# PWR.net
KiCad netlist of a schematic drawn in Altium Designer
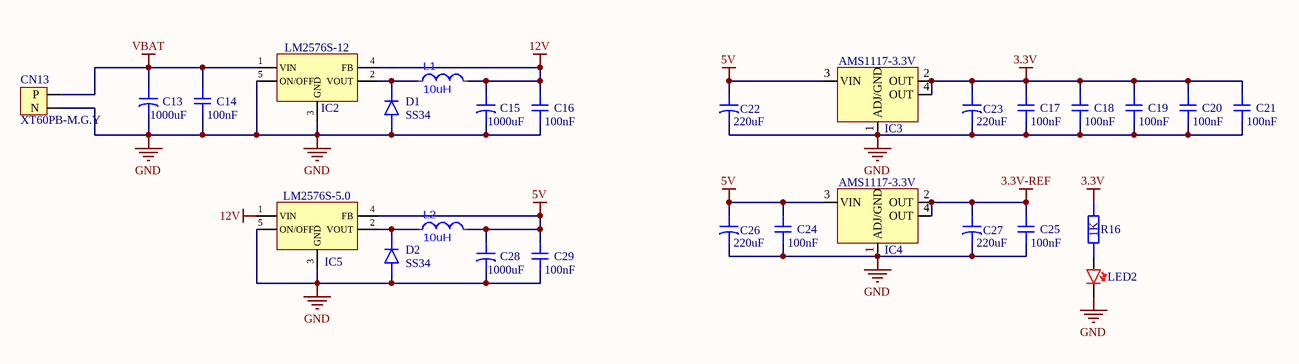
[diagram p0: PWR.SchDoc]

(export (version "E")
  (design (tool "Eeschema 10.0.6"))
  (components
    (comp (ref "C13")
      (value "1000uF")
      (footprint "Plugin,D10xL20mm")
      (description "1000uF 35V Aluminum Electrolytic Capacitors Through Hole,D10xL20mm 2000hrs@105℃")
      (fields (field (name "MANUFACTURER") "Rubycon") (field (name "MFR.PART #") "35PX1000MEFC10X20"))
      (libsource (lib "CbyP") (part "35PX1000MEFC10X20"))
    )
    (comp (ref "C14")
      (value "100nF")
      (footprint "CAP-0603-2")
      (description "100nF ±10% 50V Ceramic Capacitor X7R 0603")
      (fields (field (name "MANUFACTURER") "Samsung Electro-Mechanics") (field (name "LCSC PART #") "C1591"))
      (libsource (lib "CbyP") (part "CL10B104KB8NNNC"))
    )
    (comp (ref "C15")
      (value "1000uF")
      (footprint "Plugin,D10xL20mm")
      (description "1000uF 35V Aluminum Electrolytic Capacitors Through Hole,D10xL20mm 2000hrs@105℃")
      (fields (field (name "MANUFACTURER") "Rubycon") (field (name "MFR.PART #") "35PX1000MEFC10X20"))
      (libsource (lib "CbyP") (part "35PX1000MEFC10X20"))
    )
    (comp (ref "C16")
      (value "100nF")
      (footprint "CAP-0603-2")
      (description "100nF ±10% 50V Ceramic Capacitor X7R 0603")
      (fields (field (name "MANUFACTURER") "Samsung Electro-Mechanics") (field (name "LCSC PART #") "C1591"))
      (libsource (lib "CbyP") (part "CL10B104KB8NNNC"))
    )
    (comp (ref "C17")
      (value "100nF")
      (footprint "CAP-0603-2")
      (description "100nF ±10% 50V Ceramic Capacitor X7R 0603")
      (fields (field (name "MANUFACTURER") "Samsung Electro-Mechanics") (field (name "LCSC PART #") "C1591"))
      (libsource (lib "CbyP") (part "CL10B104KB8NNNC"))
    )
    (comp (ref "C18")
      (value "100nF")
      (footprint "CAP-0603-2")
      (description "100nF ±10% 50V Ceramic Capacitor X7R 0603")
      (fields (field (name "MANUFACTURER") "Samsung Electro-Mechanics") (field (name "LCSC PART #") "C1591"))
      (libsource (lib "CbyP") (part "CL10B104KB8NNNC"))
    )
    (comp (ref "C19")
      (value "100nF")
      (footprint "CAP-0603-2")
      (description "100nF ±10% 50V Ceramic Capacitor X7R 0603")
      (fields (field (name "MANUFACTURER") "Samsung Electro-Mechanics") (field (name "LCSC PART #") "C1591"))
      (libsource (lib "CbyP") (part "CL10B104KB8NNNC"))
    )
    (comp (ref "C20")
      (value "100nF")
      (footprint "CAP-0603-2")
      (description "100nF ±10% 50V Ceramic Capacitor X7R 0603")
      (fields (field (name "MANUFACTURER") "Samsung Electro-Mechanics") (field (name "LCSC PART #") "C1591"))
      (libsource (lib "CbyP") (part "CL10B104KB8NNNC"))
    )
    (comp (ref "C21")
      (value "100nF")
      (footprint "CAP-0603-2")
      (description "100nF ±10% 50V Ceramic Capacitor X7R 0603")
      (fields (field (name "MANUFACTURER") "Samsung Electro-Mechanics") (field (name "LCSC PART #") "C1591"))
      (libsource (lib "CbyP") (part "CL10B104KB8NNNC"))
    )
    (comp (ref "C22")
      (value "220uF")
      (footprint "PLUGIN,D6.3xL12mm")
      (description "220uF 25V Aluminum Electrolytic Capacitors Through Hole,D6.3xL11mm 7000hrs@105℃")
      (fields (field (name "MANUFACTURER") "Rubycon") (field (name "MFR.PART #") "25YXJ220M6.3X11"))
      (libsource (lib "CbyP") (part "25YXJ220M6.3X11"))
    )
    (comp (ref "C23")
      (value "220uF")
      (footprint "PLUGIN,D6.3xL12mm")
      (description "220uF 25V Aluminum Electrolytic Capacitors Through Hole,D6.3xL11mm 7000hrs@105℃")
      (fields (field (name "MANUFACTURER") "Rubycon") (field (name "MFR.PART #") "25YXJ220M6.3X11"))
      (libsource (lib "CbyP") (part "25YXJ220M6.3X11"))
    )
    (comp (ref "C24")
      (value "100nF")
      (footprint "CAP-0603-2")
      (description "100nF ±10% 50V Ceramic Capacitor X7R 0603")
      (fields (field (name "MANUFACTURER") "Samsung Electro-Mechanics") (field (name "LCSC PART #") "C1591"))
      (libsource (lib "CbyP") (part "CL10B104KB8NNNC"))
    )
    (comp (ref "C25")
      (value "100nF")
      (footprint "CAP-0603-2")
      (description "100nF ±10% 50V Ceramic Capacitor X7R 0603")
      (fields (field (name "MANUFACTURER") "Samsung Electro-Mechanics") (field (name "LCSC PART #") "C1591"))
      (libsource (lib "CbyP") (part "CL10B104KB8NNNC"))
    )
    (comp (ref "C26")
      (value "220uF")
      (footprint "PLUGIN,D6.3xL12mm")
      (description "220uF 25V Aluminum Electrolytic Capacitors Through Hole,D6.3xL11mm 7000hrs@105℃")
      (fields (field (name "MANUFACTURER") "Rubycon") (field (name "MFR.PART #") "25YXJ220M6.3X11"))
      (libsource (lib "CbyP") (part "25YXJ220M6.3X11"))
    )
    (comp (ref "C27")
      (value "220uF")
      (footprint "PLUGIN,D6.3xL12mm")
      (description "220uF 25V Aluminum Electrolytic Capacitors Through Hole,D6.3xL11mm 7000hrs@105℃")
      (fields (field (name "MANUFACTURER") "Rubycon") (field (name "MFR.PART #") "25YXJ220M6.3X11"))
      (libsource (lib "CbyP") (part "25YXJ220M6.3X11"))
    )
    (comp (ref "C28")
      (value "1000uF")
      (footprint "Plugin,D10xL20mm")
      (description "1000uF 35V Aluminum Electrolytic Capacitors Through Hole,D10xL20mm 2000hrs@105℃")
      (fields (field (name "MANUFACTURER") "Rubycon") (field (name "MFR.PART #") "35PX1000MEFC10X20"))
      (libsource (lib "CbyP") (part "35PX1000MEFC10X20"))
    )
    (comp (ref "C29")
      (value "100nF")
      (footprint "CAP-0603-2")
      (description "100nF ±10% 50V Ceramic Capacitor X7R 0603")
      (fields (field (name "MANUFACTURER") "Samsung Electro-Mechanics") (field (name "LCSC PART #") "C1591"))
      (libsource (lib "CbyP") (part "CL10B104KB8NNNC"))
    )
    (comp (ref "CN13")
      (value "XT60PB-M.G.Y")
      (footprint "XT60PB-M.G.Y")
      (description "Power Connectors RoHS")
      (fields (field (name "MANUFACTURER") "Changzhou Amass Elec") (field (name "LCSC PART #") "C19268037"))
      (libsource (lib "CbyP") (part "XT60PB-M.G.Y"))
    )
    (comp (ref "D1")
      (value "SS34")
      (footprint "SMA(DO-214AC)")
      (description "Diode Independent 40V 3A Surface Mount SMA(DO-214AC)")
      (fields (field (name "MANUFACTURER") "GOODWORK") (field (name "LCSC PART #") "C908680"))
      (libsource (lib "CbyP") (part "SS34"))
    )
    (comp (ref "D2")
      (value "SS34")
      (footprint "SMA(DO-214AC)")
      (description "Diode Independent 40V 3A Surface Mount SMA(DO-214AC)")
      (fields (field (name "MANUFACTURER") "GOODWORK") (field (name "LCSC PART #") "C908680"))
      (libsource (lib "CbyP") (part "SS34"))
    )
    (comp (ref "IC2")
      (value "LM2576S-12")
      (footprint "TO-263-5L")
      (description "Buck Switching Regulator IC Fixed 12V 1 Output 3A TO-263-5L")
      (fields (field (name "MANUFACTURER") "HXY MOSFET") (field (name "LCSC PART #") "C22386541"))
      (libsource (lib "CbyP") (part "LM2576S-12"))
    )
    (comp (ref "IC3")
      (value "AMS1117-3.3V")
      (footprint "SOT-223")
      (description "Linear Voltage Regulator IC Positive Fixed 1 Output 1A SOT-223")
      (fields (field (name "MANUFACTURER") "MSKSEMI") (field (name "LCSC PART #") "C5120765"))
      (libsource (lib "CbyP") (part "AMS1117-3.3V"))
    )
    (comp (ref "IC4")
      (value "AMS1117-3.3V")
      (footprint "SOT-223")
      (description "Linear Voltage Regulator IC Positive Fixed 1 Output 1A SOT-223")
      (fields (field (name "MANUFACTURER") "MSKSEMI") (field (name "LCSC PART #") "C5120765"))
      (libsource (lib "CbyP") (part "AMS1117-3.3V"))
    )
    (comp (ref "IC5")
      (value "LM2576S-5.0")
      (footprint "TO-263-5L")
      (description "47kHz~58kHz Buck Adjustable 3.5A 5V TO-263-5L Voltage Regulators - DC DC Switching Regulators RoHS")
      (fields (field (name "MANUFACTURER") "HXY MOSFET") (field (name "LCSC PART #") "C5349983"))
      (libsource (lib "CbyP") (part "LM2576S-5.0"))
    )
    (comp (ref "L1")
      (value "10uH")
      (footprint "Inductor 4.5A 10uH 0630")
      (description "4.5A 10uH ±20% 5.5A 68mΩ Molded Inductor SMD,7.3x6.6mm Fixed Inductors RoHS")
      (fields (field (name "MANUFACTURER") "Shun Xiang Nuo") (field (name "MPN") "SMMS0630-100M"))
      (libsource (lib "XE_BIA") (part "Inductor 4.5A 10uH 0630"))
    )
    (comp (ref "L2")
      (value "10uH")
      (footprint "Inductor 4.5A 10uH 0630")
      (description "4.5A 10uH ±20% 5.5A 68mΩ Molded Inductor SMD,7.3x6.6mm Fixed Inductors RoHS")
      (fields (field (name "MANUFACTURER") "Shun Xiang Nuo") (field (name "MPN") "SMMS0630-100M"))
      (libsource (lib "XE_BIA") (part "Inductor 4.5A 10uH 0630"))
    )
    (comp (ref "LED2")
      (value "RED")
      (footprint "LED-0603")
      (description "25mA 1.8V~2.4V Red 0603 LED Indication - Discrete ROHS")
      (fields (field (name "MANUFACTURER") "YONGYUTAI") (field (name "MFR.PART #") "YLED0603R"))
      (libsource (lib "CbyP") (part "YLED0603R"))
    )
    (comp (ref "R16")
      (value "1K")
      (footprint "RES-0603-1")
      (description "100mW 1kΩ 75V Thick Film Resistor ±100ppm/℃ ±1% 0603 Chip Resistor - Surface Mount RoHS")
      (fields (field (name "MANUFACTURER") "YAGEO") (field (name "MFR.PART #") "RC0603FR-071KL"))
      (libsource (lib "CbyP") (part "RC0603FR-071KL"))
    )
  )
  (nets
    (net (code "1") (name "3.3V") (class "Default")
      (node (ref "C17") (pin "1") (pinfunction "1_1") (pintype "passive"))
      (node (ref "C18") (pin "1") (pinfunction "1_1") (pintype "passive"))
      (node (ref "C19") (pin "1") (pinfunction "1_1") (pintype "passive"))
      (node (ref "C20") (pin "1") (pinfunction "1_1") (pintype "passive"))
      (node (ref "C21") (pin "1") (pinfunction "1_1") (pintype "passive"))
      (node (ref "C23") (pin "1") (pinfunction "1_1") (pintype "passive"))
      (node (ref "IC3") (pin "2") (pinfunction "OUT_2") (pintype "passive"))
      (node (ref "IC3") (pin "4") (pinfunction "OUT_4") (pintype "passive"))
      (node (ref "R16") (pin "2") (pinfunction "2_2") (pintype "passive"))
    )
    (net (code "2") (name "3.3V-REF") (class "Default")
      (node (ref "C25") (pin "1") (pinfunction "1_1") (pintype "passive"))
      (node (ref "C27") (pin "1") (pinfunction "1_1") (pintype "passive"))
      (node (ref "IC4") (pin "2") (pinfunction "OUT_2") (pintype "passive"))
      (node (ref "IC4") (pin "4") (pinfunction "OUT_4") (pintype "passive"))
    )
    (net (code "3") (name "5V") (class "Default")
      (node (ref "C22") (pin "1") (pinfunction "1_1") (pintype "passive"))
      (node (ref "C24") (pin "1") (pinfunction "1_1") (pintype "passive"))
      (node (ref "C26") (pin "1") (pinfunction "1_1") (pintype "passive"))
      (node (ref "C28") (pin "1") (pinfunction "1_1") (pintype "passive"))
      (node (ref "C29") (pin "1") (pinfunction "1_1") (pintype "passive"))
      (node (ref "IC3") (pin "3") (pinfunction "VIN_3") (pintype "passive"))
      (node (ref "IC4") (pin "3") (pinfunction "VIN_3") (pintype "passive"))
      (node (ref "IC5") (pin "4") (pinfunction "FB_4") (pintype "passive"))
      (node (ref "L2") (pin "2") (pinfunction "2_2") (pintype "passive"))
    )
    (net (code "4") (name "12V") (class "Default")
      (node (ref "C15") (pin "1") (pinfunction "1_1") (pintype "passive"))
      (node (ref "C16") (pin "1") (pinfunction "1_1") (pintype "passive"))
      (node (ref "IC2") (pin "4") (pinfunction "FB_4") (pintype "passive"))
      (node (ref "IC5") (pin "1") (pinfunction "VIN_1") (pintype "passive"))
      (node (ref "L1") (pin "2") (pinfunction "2_2") (pintype "passive"))
    )
    (net (code "5") (name "GND") (class "Default")
      (node (ref "C13") (pin "2") (pinfunction "2_2") (pintype "passive"))
      (node (ref "C14") (pin "2") (pinfunction "2_2") (pintype "passive"))
      (node (ref "C15") (pin "2") (pinfunction "2_2") (pintype "passive"))
      (node (ref "C16") (pin "2") (pinfunction "2_2") (pintype "passive"))
      (node (ref "C17") (pin "2") (pinfunction "2_2") (pintype "passive"))
      (node (ref "C18") (pin "2") (pinfunction "2_2") (pintype "passive"))
      (node (ref "C19") (pin "2") (pinfunction "2_2") (pintype "passive"))
      (node (ref "C20") (pin "2") (pinfunction "2_2") (pintype "passive"))
      (node (ref "C21") (pin "2") (pinfunction "2_2") (pintype "passive"))
      (node (ref "C22") (pin "2") (pinfunction "2_2") (pintype "passive"))
      (node (ref "C23") (pin "2") (pinfunction "2_2") (pintype "passive"))
      (node (ref "C24") (pin "2") (pinfunction "2_2") (pintype "passive"))
      (node (ref "C25") (pin "2") (pinfunction "2_2") (pintype "passive"))
      (node (ref "C26") (pin "2") (pinfunction "2_2") (pintype "passive"))
      (node (ref "C27") (pin "2") (pinfunction "2_2") (pintype "passive"))
      (node (ref "C28") (pin "2") (pinfunction "2_2") (pintype "passive"))
      (node (ref "C29") (pin "2") (pinfunction "2_2") (pintype "passive"))
      (node (ref "CN13") (pin "2") (pinfunction "N_2") (pintype "passive"))
      (node (ref "D1") (pin "1") (pinfunction "A_1") (pintype "passive"))
      (node (ref "D2") (pin "1") (pinfunction "A_1") (pintype "passive"))
      (node (ref "IC2") (pin "3") (pinfunction "GND_3") (pintype "passive"))
      (node (ref "IC2") (pin "5") (pinfunction "ON/OFF_5") (pintype "passive"))
      (node (ref "IC3") (pin "1") (pinfunction "ADJ/GND_1") (pintype "passive"))
      (node (ref "IC4") (pin "1") (pinfunction "ADJ/GND_1") (pintype "passive"))
      (node (ref "IC5") (pin "3") (pinfunction "GND_3") (pintype "passive"))
      (node (ref "IC5") (pin "5") (pinfunction "ON/OFF_5") (pintype "passive"))
      (node (ref "LED2") (pin "2") (pinfunction "K_2") (pintype "passive"))
    )
    (net (code "6") (name "Net-(D1-K)") (class "Default")
      (node (ref "D1") (pin "2") (pinfunction "K_2") (pintype "passive"))
      (node (ref "IC2") (pin "2") (pinfunction "VOUT_2") (pintype "passive"))
      (node (ref "L1") (pin "1") (pinfunction "1_1") (pintype "passive"))
    )
    (net (code "7") (name "Net-(D2-K)") (class "Default")
      (node (ref "D2") (pin "2") (pinfunction "K_2") (pintype "passive"))
      (node (ref "IC5") (pin "2") (pinfunction "VOUT_2") (pintype "passive"))
      (node (ref "L2") (pin "1") (pinfunction "1_1") (pintype "passive"))
    )
    (net (code "8") (name "Net-(LED2-A)") (class "Default")
      (node (ref "LED2") (pin "1") (pinfunction "A_1") (pintype "passive"))
      (node (ref "R16") (pin "1") (pinfunction "1_1") (pintype "passive"))
    )
    (net (code "9") (name "VBAT") (class "Default")
      (node (ref "C13") (pin "1") (pinfunction "1_1") (pintype "passive"))
      (node (ref "C14") (pin "1") (pinfunction "1_1") (pintype "passive"))
      (node (ref "CN13") (pin "1") (pinfunction "P_1") (pintype "passive"))
      (node (ref "IC2") (pin "1") (pinfunction "VIN_1") (pintype "passive"))
    )
  )
)
